# IHM.net
KiCad netlist of a schematic drawn in EAGLE
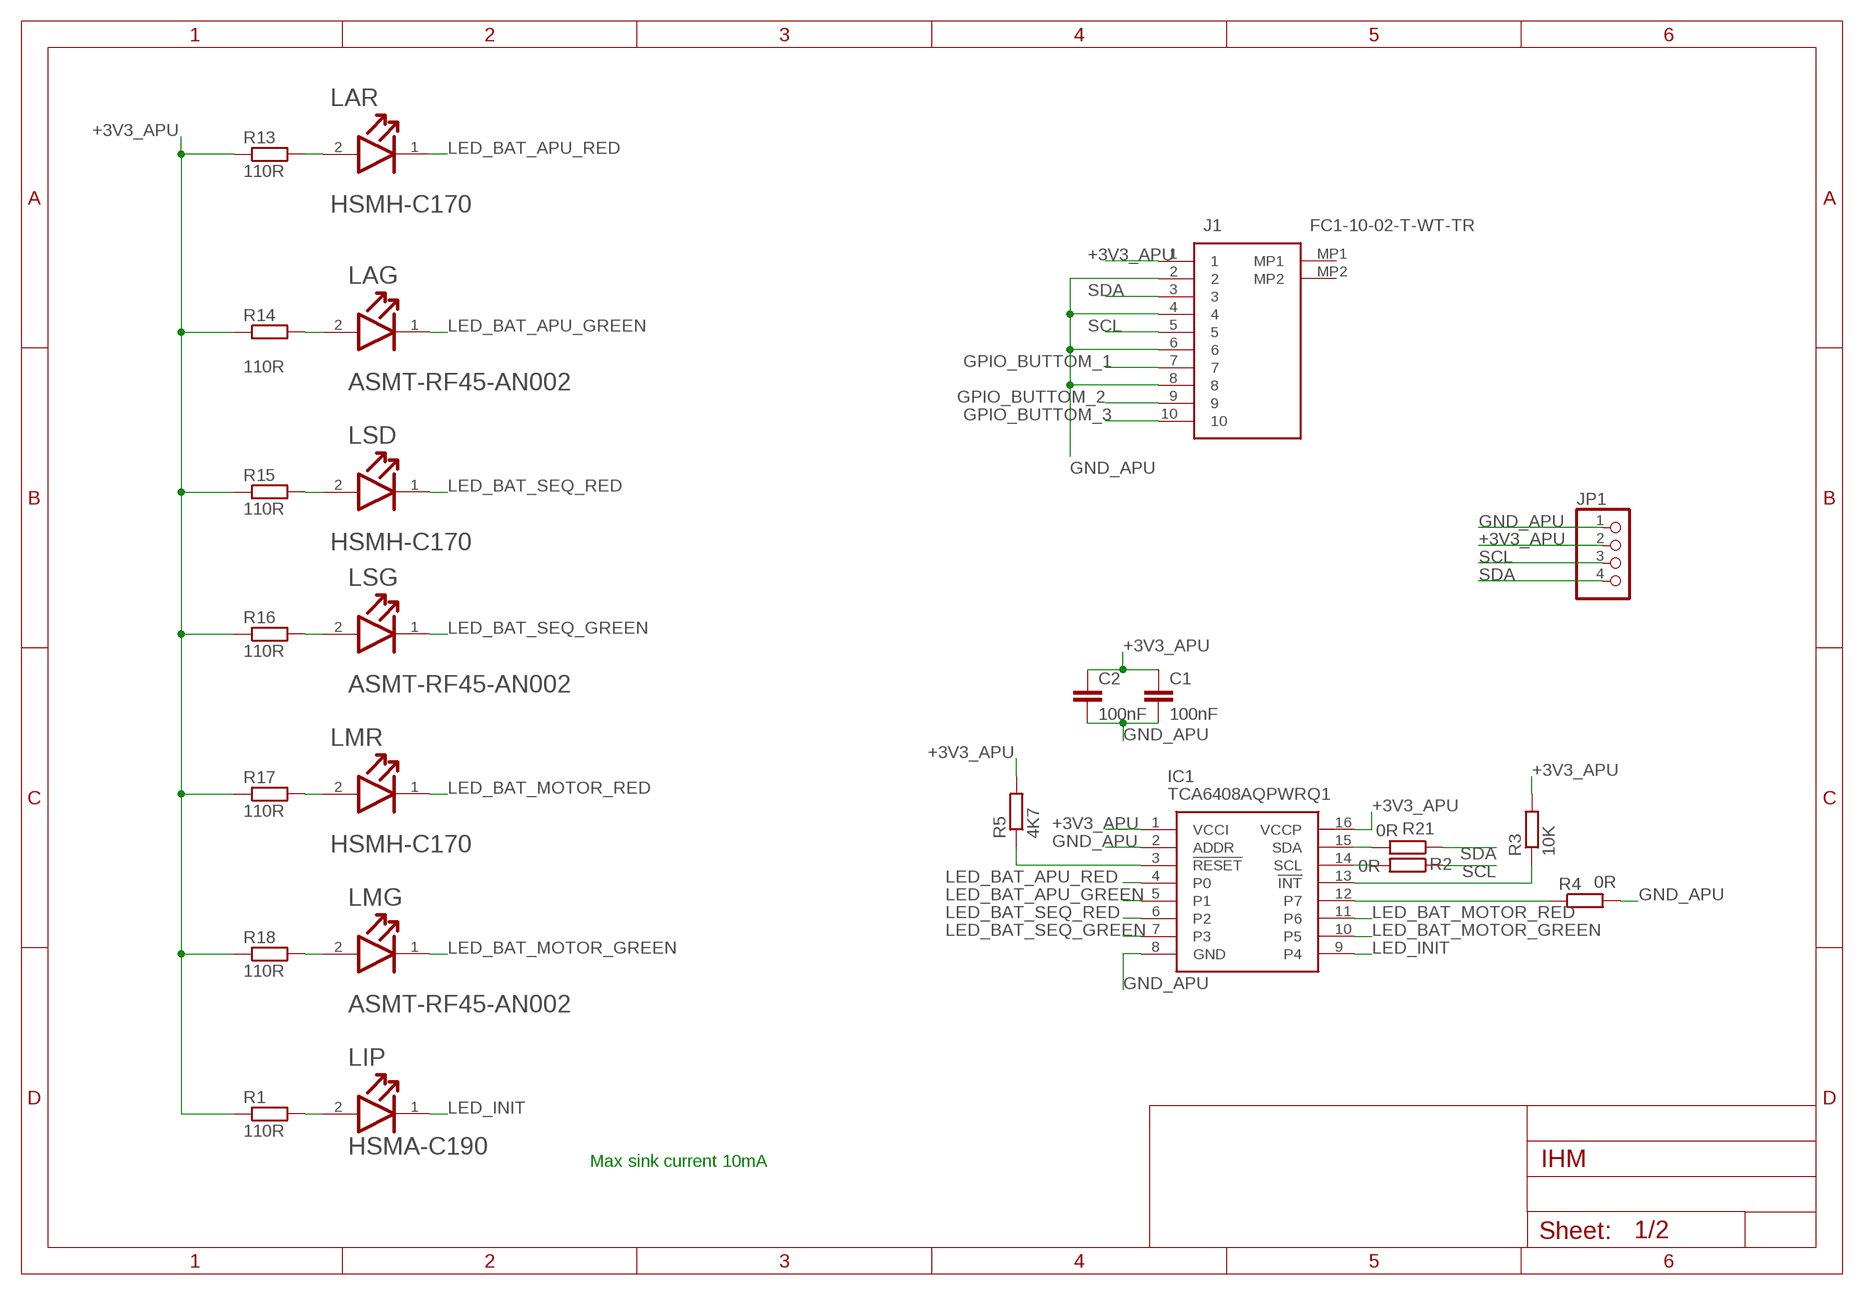
[diagram p0: schematic, sheet 1]
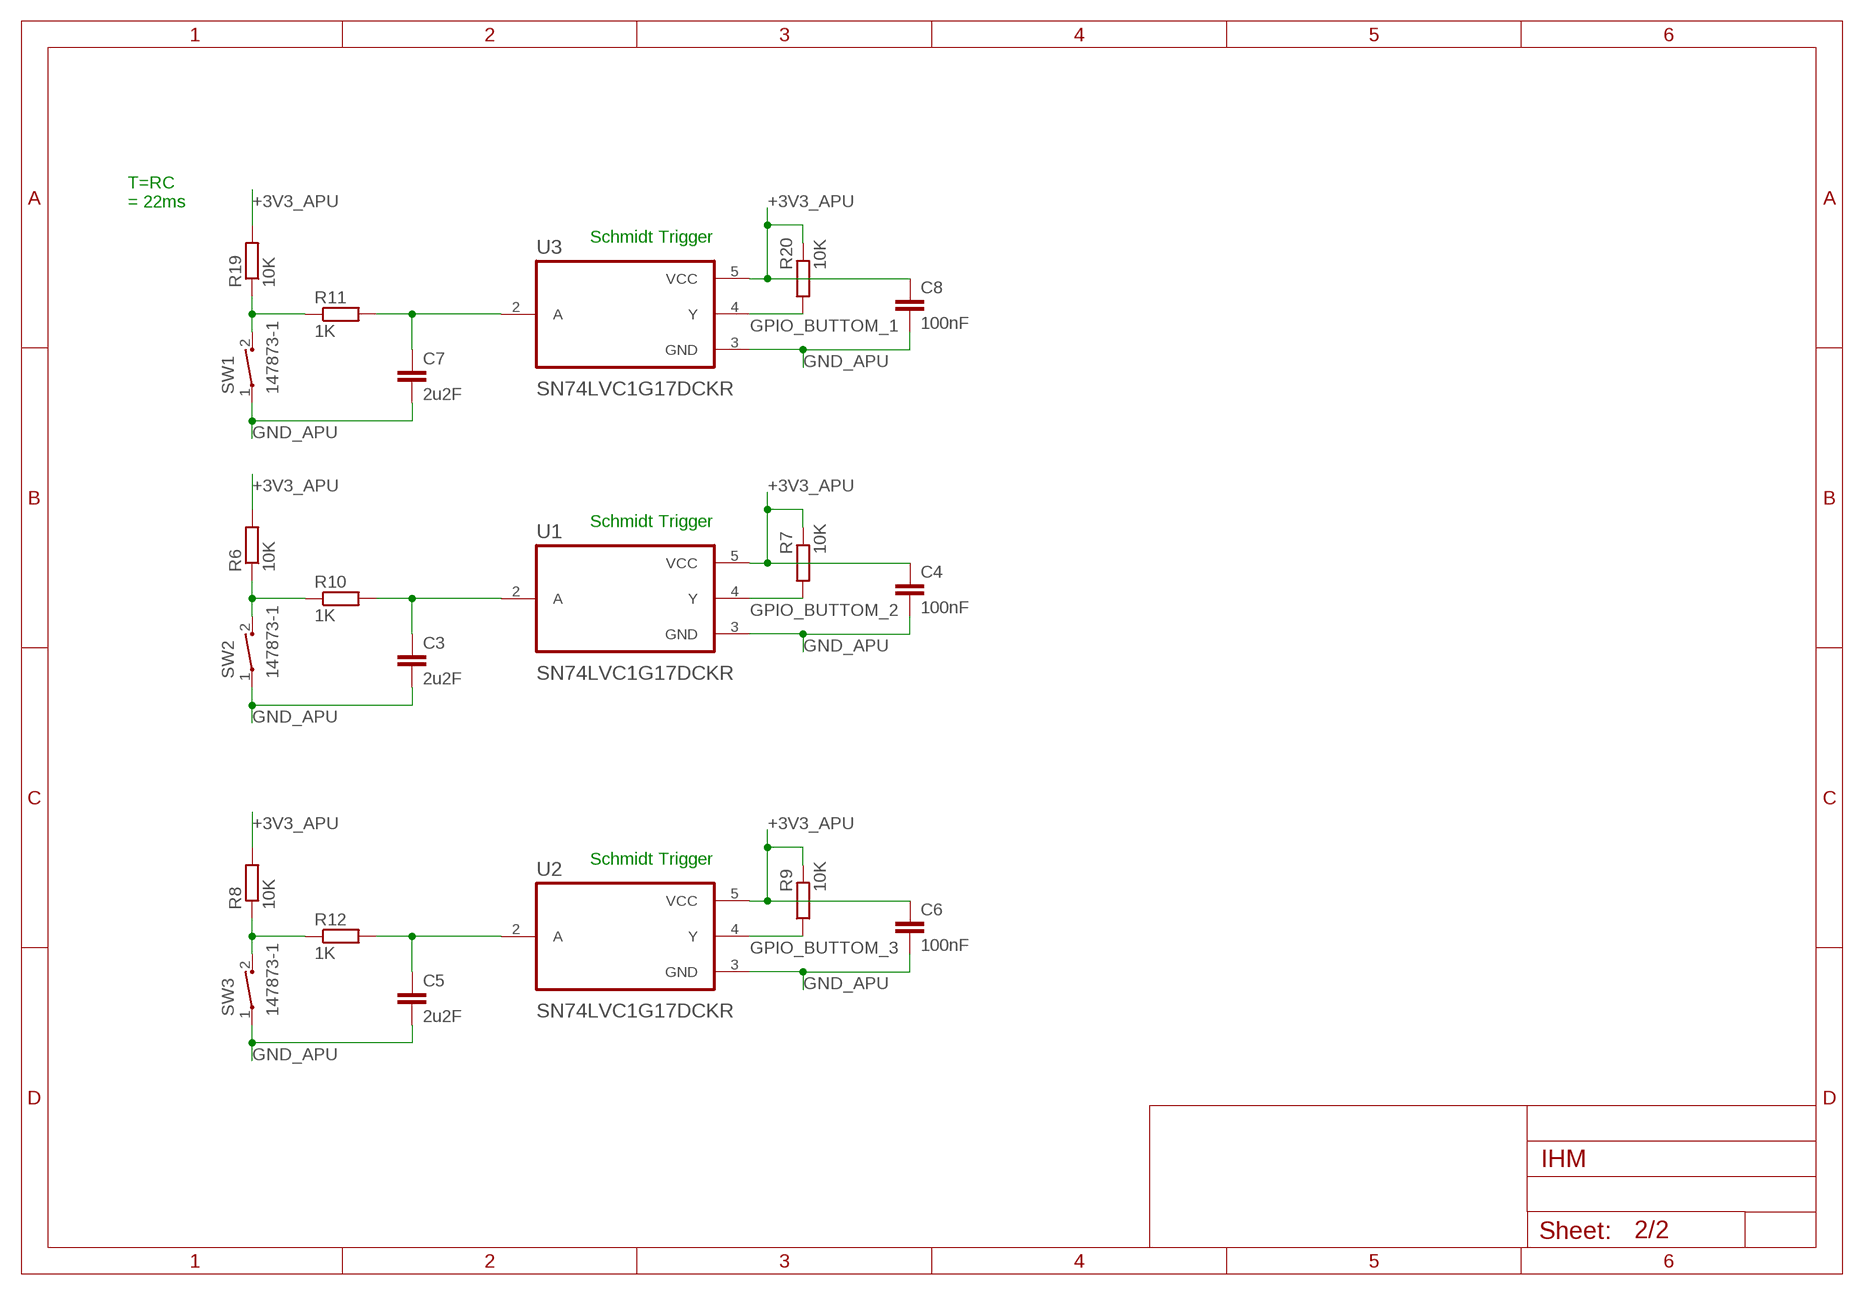
[diagram p1: schematic, sheet 2]

(export (version "E")
  (design (tool "Eeschema 10.0.6"))
  (components
    (comp (ref "C3")
      (value "2u2F")
      (footprint "eagle-import:C0805K")
      (libsource (lib "eagle-import") (part "C-EUC0805K"))
    )
    (comp (ref "C4")
      (value "100nF")
      (footprint "eagle-import:C0805K")
      (libsource (lib "eagle-import") (part "C-EUC0805K"))
    )
    (comp (ref "C5")
      (value "2u2F")
      (footprint "eagle-import:C0805K")
      (libsource (lib "eagle-import") (part "C-EUC0805K"))
    )
    (comp (ref "C6")
      (value "100nF")
      (footprint "eagle-import:C0805K")
      (libsource (lib "eagle-import") (part "C-EUC0805K"))
    )
    (comp (ref "C7")
      (value "2u2F")
      (footprint "eagle-import:C0805K")
      (libsource (lib "eagle-import") (part "C-EUC0805K"))
    )
    (comp (ref "C8")
      (value "100nF")
      (footprint "eagle-import:C0805K")
      (libsource (lib "eagle-import") (part "C-EUC0805K"))
    )
    (comp (ref "R6")
      (value "10K")
      (footprint "eagle-import:R0603")
      (libsource (lib "eagle-import") (part "R-EU_R0603"))
    )
    (comp (ref "R7")
      (value "10K")
      (footprint "eagle-import:R0603")
      (libsource (lib "eagle-import") (part "R-EU_R0603"))
    )
    (comp (ref "R8")
      (value "10K")
      (footprint "eagle-import:R0603")
      (libsource (lib "eagle-import") (part "R-EU_R0603"))
    )
    (comp (ref "R9")
      (value "10K")
      (footprint "eagle-import:R0603")
      (libsource (lib "eagle-import") (part "R-EU_R0603"))
    )
    (comp (ref "R10")
      (value "1K")
      (footprint "eagle-import:R0603")
      (libsource (lib "eagle-import") (part "R-EU_R0603"))
    )
    (comp (ref "R11")
      (value "1K")
      (footprint "eagle-import:R0603")
      (libsource (lib "eagle-import") (part "R-EU_R0603"))
    )
    (comp (ref "R12")
      (value "1K")
      (footprint "eagle-import:R0603")
      (libsource (lib "eagle-import") (part "R-EU_R0603"))
    )
    (comp (ref "R19")
      (value "10K")
      (footprint "eagle-import:R0603")
      (libsource (lib "eagle-import") (part "R-EU_R0603"))
    )
    (comp (ref "R20")
      (value "10K")
      (footprint "eagle-import:R0603")
      (libsource (lib "eagle-import") (part "R-EU_R0603"))
    )
    (comp (ref "SW1")
      (value "147873-1")
      (footprint "eagle-import:SW_147873-1")
      (fields (field (name "MF") "TE Connectivity"))
      (libsource (lib "eagle-import") (part "147873-1"))
    )
    (comp (ref "SW2")
      (value "147873-1")
      (footprint "eagle-import:SW_147873-1")
      (fields (field (name "MF") "TE Connectivity"))
      (libsource (lib "eagle-import") (part "147873-1"))
    )
    (comp (ref "SW3")
      (value "147873-1")
      (footprint "eagle-import:SW_147873-1")
      (fields (field (name "MF") "TE Connectivity"))
      (libsource (lib "eagle-import") (part "147873-1"))
    )
    (comp (ref "U1")
      (value "SN74LVC1G17DCKR")
      (footprint "eagle-import:SOT65P210X110-5N")
      (fields (field (name "MF") "Texas Instruments"))
      (libsource (lib "eagle-import") (part "SN74LVC1G17DCKR"))
    )
    (comp (ref "U2")
      (value "SN74LVC1G17DCKR")
      (footprint "eagle-import:SOT65P210X110-5N")
      (fields (field (name "MF") "Texas Instruments"))
      (libsource (lib "eagle-import") (part "SN74LVC1G17DCKR"))
    )
    (comp (ref "U3")
      (value "SN74LVC1G17DCKR")
      (footprint "eagle-import:SOT65P210X110-5N")
      (fields (field (name "MF") "Texas Instruments"))
      (libsource (lib "eagle-import") (part "SN74LVC1G17DCKR"))
    )
    (comp (ref "C1")
      (value "100nF")
      (footprint "eagle-import:C0805")
      (libsource (lib "eagle-import") (part "C-EUC0805"))
    )
    (comp (ref "C2")
      (value "100nF")
      (footprint "eagle-import:C0805")
      (libsource (lib "eagle-import") (part "C-EUC0805"))
    )
    (comp (ref "IC1")
      (value "TCA6408AQPWRQ1")
      (footprint "eagle-import:SOP65P640X120-16N")
      (fields (field (name "MOUSER_PART_NUMBER") "595-TCA6408AQPWRQ1"))
      (libsource (lib "eagle-import") (part "TCA6408AQPWRQ1"))
    )
    (comp (ref "J1")
      (value "FC1-10-02-T-WT-TR")
      (footprint "eagle-import:FC11002TWTTR")
      (fields (field (name "MOUSER_PART_NUMBER") "200-FC11002TWTTR"))
      (libsource (lib "eagle-import") (part "FC1-10-02-T-WT-TR"))
    )
    (comp (ref "JP1")
      (value "PINHD-1X4")
      (footprint "eagle-import:1X04")
      (libsource (lib "eagle-import") (part "PINHD-1X4"))
    )
    (comp (ref "LAG")
      (value "BROADCOM_ASMT-RF45-AN002BROADCOM_ASMT-RF45-AN002_0_0")
      (footprint "eagle-import:BROADCOM_ASMT-RF45-AN002_0")
      (fields
        (field (name "DIGIKEY_PART_NUMBER") "516-2522-1-ND")
        (field (name "MF") "Broadcom")
        (field (name "MOUSER_PART_NUMBER") "630-ASMT-RF45-AN002")
      )
      (libsource (lib "eagle-import") (part "BROADCOM_ASMT-RF45-AN002BROADCOM_ASMT-RF45-AN002_0_0"))
    )
    (comp (ref "LAR")
      (value "BROADCOM_HSMH-C170BROADCOM_HSMH-C170_0_0")
      (footprint "eagle-import:BROADCOM_HSMH-C170_0")
      (fields
        (field (name "DIGIKEY_PART_NUMBER") "516-1427-1-ND")
        (field (name "MF") "Broadcom")
        (field (name "MOUSER_PART_NUMBER") "630-HSMH-C170")
      )
      (libsource (lib "eagle-import") (part "BROADCOM_HSMH-C170BROADCOM_HSMH-C170_0_0"))
    )
    (comp (ref "LIP")
      (value "BROADCOM_HSMA-C190BROADCOM_HSMA-C190_0_0")
      (footprint "eagle-import:BROADCOM_HSMA-C190_0")
      (fields
        (field (name "DIGIKEY_PART_NUMBER") "516-1423-1-ND")
        (field (name "MF") "Broadcom")
        (field (name "MOUSER_PART_NUMBER") "630-HSMA-C190")
      )
      (libsource (lib "eagle-import") (part "BROADCOM_HSMA-C190BROADCOM_HSMA-C190_0_0"))
    )
    (comp (ref "LMG")
      (value "BROADCOM_ASMT-RF45-AN002BROADCOM_ASMT-RF45-AN002_0_0")
      (footprint "eagle-import:BROADCOM_ASMT-RF45-AN002_0")
      (fields
        (field (name "DIGIKEY_PART_NUMBER") "516-2522-1-ND")
        (field (name "MF") "Broadcom")
        (field (name "MOUSER_PART_NUMBER") "630-ASMT-RF45-AN002")
      )
      (libsource (lib "eagle-import") (part "BROADCOM_ASMT-RF45-AN002BROADCOM_ASMT-RF45-AN002_0_0"))
    )
    (comp (ref "LMR")
      (value "BROADCOM_HSMH-C170BROADCOM_HSMH-C170_0_0")
      (footprint "eagle-import:BROADCOM_HSMH-C170_0")
      (fields
        (field (name "DIGIKEY_PART_NUMBER") "516-1427-1-ND")
        (field (name "MF") "Broadcom")
        (field (name "MOUSER_PART_NUMBER") "630-HSMH-C170")
      )
      (libsource (lib "eagle-import") (part "BROADCOM_HSMH-C170BROADCOM_HSMH-C170_0_0"))
    )
    (comp (ref "LSD")
      (value "BROADCOM_HSMH-C170BROADCOM_HSMH-C170_0_0")
      (footprint "eagle-import:BROADCOM_HSMH-C170_0")
      (fields
        (field (name "DIGIKEY_PART_NUMBER") "516-1427-1-ND")
        (field (name "MF") "Broadcom")
        (field (name "MOUSER_PART_NUMBER") "630-HSMH-C170")
      )
      (libsource (lib "eagle-import") (part "BROADCOM_HSMH-C170BROADCOM_HSMH-C170_0_0"))
    )
    (comp (ref "LSG")
      (value "BROADCOM_ASMT-RF45-AN002BROADCOM_ASMT-RF45-AN002_0_0")
      (footprint "eagle-import:BROADCOM_ASMT-RF45-AN002_0")
      (fields
        (field (name "DIGIKEY_PART_NUMBER") "516-2522-1-ND")
        (field (name "MF") "Broadcom")
        (field (name "MOUSER_PART_NUMBER") "630-ASMT-RF45-AN002")
      )
      (libsource (lib "eagle-import") (part "BROADCOM_ASMT-RF45-AN002BROADCOM_ASMT-RF45-AN002_0_0"))
    )
    (comp (ref "R1")
      (value "110R")
      (footprint "eagle-import:R0603")
      (libsource (lib "eagle-import") (part "R-EU_R0603"))
    )
    (comp (ref "R2")
      (value "0R")
      (footprint "eagle-import:R0603")
      (libsource (lib "eagle-import") (part "R-EU_R0603"))
    )
    (comp (ref "R3")
      (value "10K")
      (footprint "eagle-import:R0603")
      (libsource (lib "eagle-import") (part "R-EU_R0603"))
    )
    (comp (ref "R4")
      (value "0R")
      (footprint "eagle-import:R0603")
      (libsource (lib "eagle-import") (part "R-EU_R0603"))
    )
    (comp (ref "R5")
      (value "4K7")
      (footprint "eagle-import:R0603")
      (libsource (lib "eagle-import") (part "R-EU_R0603"))
    )
    (comp (ref "R13")
      (value "110R")
      (footprint "eagle-import:R0603")
      (libsource (lib "eagle-import") (part "R-EU_R0603"))
    )
    (comp (ref "R14")
      (value "110R")
      (footprint "eagle-import:R0603")
      (libsource (lib "eagle-import") (part "R-EU_R0603"))
    )
    (comp (ref "R15")
      (value "110R")
      (footprint "eagle-import:R0603")
      (libsource (lib "eagle-import") (part "R-EU_R0603"))
    )
    (comp (ref "R16")
      (value "110R")
      (footprint "eagle-import:R0603")
      (libsource (lib "eagle-import") (part "R-EU_R0603"))
    )
    (comp (ref "R17")
      (value "110R")
      (footprint "eagle-import:R0603")
      (libsource (lib "eagle-import") (part "R-EU_R0603"))
    )
    (comp (ref "R18")
      (value "110R")
      (footprint "eagle-import:R0603")
      (libsource (lib "eagle-import") (part "R-EU_R0603"))
    )
    (comp (ref "R21")
      (value "0R")
      (footprint "eagle-import:R0603")
      (libsource (lib "eagle-import") (part "R-EU_R0603"))
    )
  )
  (nets
    (net (code "1") (name "+3V3_APU") (class "Default")
      (node (ref "C1") (pin "1") (pinfunction "1_1") (pintype "passive"))
      (node (ref "C2") (pin "1") (pinfunction "1_1") (pintype "passive"))
      (node (ref "C4") (pin "1") (pinfunction "1_1") (pintype "passive"))
      (node (ref "C6") (pin "1") (pinfunction "1_1") (pintype "passive"))
      (node (ref "C8") (pin "1") (pinfunction "1_1") (pintype "passive"))
      (node (ref "IC1") (pin "1") (pinfunction "VCCI_1") (pintype "bidirectional"))
      (node (ref "IC1") (pin "16") (pinfunction "VCCP_16") (pintype "bidirectional"))
      (node (ref "J1") (pin "1") (pinfunction "1_1") (pintype "bidirectional"))
      (node (ref "JP1") (pin "2") (pinfunction "2_2") (pintype "passive"))
      (node (ref "R1") (pin "1") (pinfunction "1_1") (pintype "passive"))
      (node (ref "R13") (pin "1") (pinfunction "1_1") (pintype "passive"))
      (node (ref "R14") (pin "1") (pinfunction "1_1") (pintype "passive"))
      (node (ref "R15") (pin "1") (pinfunction "1_1") (pintype "passive"))
      (node (ref "R16") (pin "1") (pinfunction "1_1") (pintype "passive"))
      (node (ref "R17") (pin "1") (pinfunction "1_1") (pintype "passive"))
      (node (ref "R18") (pin "1") (pinfunction "1_1") (pintype "passive"))
      (node (ref "R19") (pin "2") (pinfunction "2_2") (pintype "passive"))
      (node (ref "R20") (pin "2") (pinfunction "2_2") (pintype "passive"))
      (node (ref "R3") (pin "2") (pinfunction "2_2") (pintype "passive"))
      (node (ref "R5") (pin "2") (pinfunction "2_2") (pintype "passive"))
      (node (ref "R6") (pin "2") (pinfunction "2_2") (pintype "passive"))
      (node (ref "R7") (pin "2") (pinfunction "2_2") (pintype "passive"))
      (node (ref "R8") (pin "2") (pinfunction "2_2") (pintype "passive"))
      (node (ref "R9") (pin "2") (pinfunction "2_2") (pintype "passive"))
      (node (ref "U1") (pin "5") (pinfunction "VCC_5") (pintype "power_in"))
      (node (ref "U2") (pin "5") (pinfunction "VCC_5") (pintype "power_in"))
      (node (ref "U3") (pin "5") (pinfunction "VCC_5") (pintype "power_in"))
    )
    (net (code "2") (name "GND_APU") (class "Default")
      (node (ref "C1") (pin "2") (pinfunction "2_2") (pintype "passive"))
      (node (ref "C2") (pin "2") (pinfunction "2_2") (pintype "passive"))
      (node (ref "C3") (pin "2") (pinfunction "2_2") (pintype "passive"))
      (node (ref "C4") (pin "2") (pinfunction "2_2") (pintype "passive"))
      (node (ref "C5") (pin "2") (pinfunction "2_2") (pintype "passive"))
      (node (ref "C6") (pin "2") (pinfunction "2_2") (pintype "passive"))
      (node (ref "C7") (pin "2") (pinfunction "2_2") (pintype "passive"))
      (node (ref "C8") (pin "2") (pinfunction "2_2") (pintype "passive"))
      (node (ref "IC1") (pin "2") (pinfunction "ADDR_2") (pintype "bidirectional"))
      (node (ref "IC1") (pin "8") (pinfunction "GND_8") (pintype "bidirectional"))
      (node (ref "J1") (pin "2") (pinfunction "2_2") (pintype "bidirectional"))
      (node (ref "J1") (pin "4") (pinfunction "4_4") (pintype "bidirectional"))
      (node (ref "J1") (pin "6") (pinfunction "6_6") (pintype "bidirectional"))
      (node (ref "J1") (pin "8") (pinfunction "8_8") (pintype "bidirectional"))
      (node (ref "JP1") (pin "1") (pinfunction "1_1") (pintype "passive"))
      (node (ref "R4") (pin "2") (pinfunction "2_2") (pintype "passive"))
      (node (ref "SW1") (pin "1") (pinfunction "1_1") (pintype "passive"))
      (node (ref "SW2") (pin "1") (pinfunction "1_1") (pintype "passive"))
      (node (ref "SW3") (pin "1") (pinfunction "1_1") (pintype "passive"))
      (node (ref "U1") (pin "3") (pinfunction "GND_3") (pintype "power_in"))
      (node (ref "U2") (pin "3") (pinfunction "GND_3") (pintype "power_in"))
      (node (ref "U3") (pin "3") (pinfunction "GND_3") (pintype "power_in"))
    )
    (net (code "3") (name "GPIO_BUTTOM_1") (class "Default")
      (node (ref "J1") (pin "7") (pinfunction "7_7") (pintype "bidirectional"))
      (node (ref "R20") (pin "1") (pinfunction "1_1") (pintype "passive"))
      (node (ref "U3") (pin "4") (pinfunction "Y_4") (pintype "output"))
    )
    (net (code "4") (name "GPIO_BUTTOM_2") (class "Default")
      (node (ref "J1") (pin "9") (pinfunction "9_9") (pintype "bidirectional"))
      (node (ref "R7") (pin "1") (pinfunction "1_1") (pintype "passive"))
      (node (ref "U1") (pin "4") (pinfunction "Y_4") (pintype "output"))
    )
    (net (code "5") (name "GPIO_BUTTOM_3") (class "Default")
      (node (ref "J1") (pin "10") (pinfunction "10_10") (pintype "bidirectional"))
      (node (ref "R9") (pin "1") (pinfunction "1_1") (pintype "passive"))
      (node (ref "U2") (pin "4") (pinfunction "Y_4") (pintype "output"))
    )
    (net (code "6") (name "LED_BAT_APU_GREEN") (class "Default")
      (node (ref "IC1") (pin "5") (pinfunction "P1_5") (pintype "bidirectional"))
      (node (ref "LAG") (pin "1") (pinfunction "CATHODE_1") (pintype "passive"))
    )
    (net (code "7") (name "LED_BAT_APU_RED") (class "Default")
      (node (ref "IC1") (pin "4") (pinfunction "P0_4") (pintype "bidirectional"))
      (node (ref "LAR") (pin "1") (pinfunction "CATHODE_1") (pintype "passive"))
    )
    (net (code "8") (name "LED_BAT_MOTOR_GREEN") (class "Default")
      (node (ref "IC1") (pin "10") (pinfunction "P5_10") (pintype "bidirectional"))
      (node (ref "LMG") (pin "1") (pinfunction "CATHODE_1") (pintype "passive"))
    )
    (net (code "9") (name "LED_BAT_MOTOR_RED") (class "Default")
      (node (ref "IC1") (pin "11") (pinfunction "P6_11") (pintype "bidirectional"))
      (node (ref "LMR") (pin "1") (pinfunction "CATHODE_1") (pintype "passive"))
    )
    (net (code "10") (name "LED_BAT_SEQ_GREEN") (class "Default")
      (node (ref "IC1") (pin "7") (pinfunction "P3_7") (pintype "bidirectional"))
      (node (ref "LSG") (pin "1") (pinfunction "CATHODE_1") (pintype "passive"))
    )
    (net (code "11") (name "LED_BAT_SEQ_RED") (class "Default")
      (node (ref "IC1") (pin "6") (pinfunction "P2_6") (pintype "bidirectional"))
      (node (ref "LSD") (pin "1") (pinfunction "CATHODE_1") (pintype "passive"))
    )
    (net (code "12") (name "LED_INIT") (class "Default")
      (node (ref "IC1") (pin "9") (pinfunction "P4_9") (pintype "bidirectional"))
      (node (ref "LIP") (pin "1") (pinfunction "CATHODE_1") (pintype "passive"))
    )
    (net (code "13") (name "Net-(IC1-P7)") (class "Default")
      (node (ref "IC1") (pin "12") (pinfunction "P7_12") (pintype "bidirectional"))
      (node (ref "R4") (pin "1") (pinfunction "1_1") (pintype "passive"))
    )
    (net (code "14") (name "Net-(IC1-SCL)") (class "Default")
      (node (ref "IC1") (pin "14") (pinfunction "SCL_14") (pintype "bidirectional"))
      (node (ref "R2") (pin "2") (pinfunction "2_2") (pintype "passive"))
    )
    (net (code "15") (name "Net-(IC1-SDA)") (class "Default")
      (node (ref "IC1") (pin "15") (pinfunction "SDA_15") (pintype "bidirectional"))
      (node (ref "R21") (pin "2") (pinfunction "2_2") (pintype "passive"))
    )
    (net (code "16") (name "Net-(IC1-~{INT})") (class "Default")
      (node (ref "IC1") (pin "13") (pinfunction "~{INT}_13") (pintype "bidirectional"))
      (node (ref "R3") (pin "1") (pinfunction "1_1") (pintype "passive"))
    )
    (net (code "17") (name "Net-(IC1-~{RESET})") (class "Default")
      (node (ref "IC1") (pin "3") (pinfunction "~{RESET}_3") (pintype "bidirectional"))
      (node (ref "R5") (pin "1") (pinfunction "1_1") (pintype "passive"))
    )
    (net (code "18") (name "Net-(LAG-ANODE)") (class "Default")
      (node (ref "LAG") (pin "2") (pinfunction "ANODE_2") (pintype "passive"))
      (node (ref "R14") (pin "2") (pinfunction "2_2") (pintype "passive"))
    )
    (net (code "19") (name "Net-(LAR-ANODE)") (class "Default")
      (node (ref "LAR") (pin "2") (pinfunction "ANODE_2") (pintype "passive"))
      (node (ref "R13") (pin "2") (pinfunction "2_2") (pintype "passive"))
    )
    (net (code "20") (name "Net-(LIP-ANODE)") (class "Default")
      (node (ref "LIP") (pin "2") (pinfunction "ANODE_2") (pintype "passive"))
      (node (ref "R1") (pin "2") (pinfunction "2_2") (pintype "passive"))
    )
    (net (code "21") (name "Net-(LMG-ANODE)") (class "Default")
      (node (ref "LMG") (pin "2") (pinfunction "ANODE_2") (pintype "passive"))
      (node (ref "R18") (pin "2") (pinfunction "2_2") (pintype "passive"))
    )
    (net (code "22") (name "Net-(LMR-ANODE)") (class "Default")
      (node (ref "LMR") (pin "2") (pinfunction "ANODE_2") (pintype "passive"))
      (node (ref "R17") (pin "2") (pinfunction "2_2") (pintype "passive"))
    )
    (net (code "23") (name "Net-(LSD-ANODE)") (class "Default")
      (node (ref "LSD") (pin "2") (pinfunction "ANODE_2") (pintype "passive"))
      (node (ref "R15") (pin "2") (pinfunction "2_2") (pintype "passive"))
    )
    (net (code "24") (name "Net-(LSG-ANODE)") (class "Default")
      (node (ref "LSG") (pin "2") (pinfunction "ANODE_2") (pintype "passive"))
      (node (ref "R16") (pin "2") (pinfunction "2_2") (pintype "passive"))
    )
    (net (code "25") (name "Net-(R10-Pad1)") (class "Default")
      (node (ref "R10") (pin "1") (pinfunction "1_1") (pintype "passive"))
      (node (ref "R6") (pin "1") (pinfunction "1_1") (pintype "passive"))
      (node (ref "SW2") (pin "2") (pinfunction "2_2") (pintype "passive"))
    )
    (net (code "26") (name "Net-(R11-Pad1)") (class "Default")
      (node (ref "R11") (pin "1") (pinfunction "1_1") (pintype "passive"))
      (node (ref "R19") (pin "1") (pinfunction "1_1") (pintype "passive"))
      (node (ref "SW1") (pin "2") (pinfunction "2_2") (pintype "passive"))
    )
    (net (code "27") (name "Net-(R12-Pad1)") (class "Default")
      (node (ref "R12") (pin "1") (pinfunction "1_1") (pintype "passive"))
      (node (ref "R8") (pin "1") (pinfunction "1_1") (pintype "passive"))
      (node (ref "SW3") (pin "2") (pinfunction "2_2") (pintype "passive"))
    )
    (net (code "28") (name "Net-(U1-A)") (class "Default")
      (node (ref "C3") (pin "1") (pinfunction "1_1") (pintype "passive"))
      (node (ref "R10") (pin "2") (pinfunction "2_2") (pintype "passive"))
      (node (ref "U1") (pin "2") (pinfunction "A_2") (pintype "input"))
    )
    (net (code "29") (name "Net-(U2-A)") (class "Default")
      (node (ref "C5") (pin "1") (pinfunction "1_1") (pintype "passive"))
      (node (ref "R12") (pin "2") (pinfunction "2_2") (pintype "passive"))
      (node (ref "U2") (pin "2") (pinfunction "A_2") (pintype "input"))
    )
    (net (code "30") (name "Net-(U3-A)") (class "Default")
      (node (ref "C7") (pin "1") (pinfunction "1_1") (pintype "passive"))
      (node (ref "R11") (pin "2") (pinfunction "2_2") (pintype "passive"))
      (node (ref "U3") (pin "2") (pinfunction "A_2") (pintype "input"))
    )
    (net (code "31") (name "SCL") (class "Default")
      (node (ref "J1") (pin "5") (pinfunction "5_5") (pintype "bidirectional"))
      (node (ref "JP1") (pin "3") (pinfunction "3_3") (pintype "passive"))
      (node (ref "R2") (pin "1") (pinfunction "1_1") (pintype "passive"))
    )
    (net (code "32") (name "SDA") (class "Default")
      (node (ref "J1") (pin "3") (pinfunction "3_3") (pintype "bidirectional"))
      (node (ref "JP1") (pin "4") (pinfunction "4_4") (pintype "passive"))
      (node (ref "R21") (pin "1") (pinfunction "1_1") (pintype "passive"))
    )
    (net (code "33") (name "unconnected-(J1-PadMP1)") (class "Default")
      (node (ref "J1") (pin "MP1") (pinfunction "MP1_MP1") (pintype "bidirectional"))
    )
    (net (code "34") (name "unconnected-(J1-PadMP2)") (class "Default")
      (node (ref "J1") (pin "MP2") (pinfunction "MP2_MP2") (pintype "bidirectional"))
    )
  )
)
